# feather-load-tester-relabeled.net
KiCad netlist of a schematic drawn in EAGLE
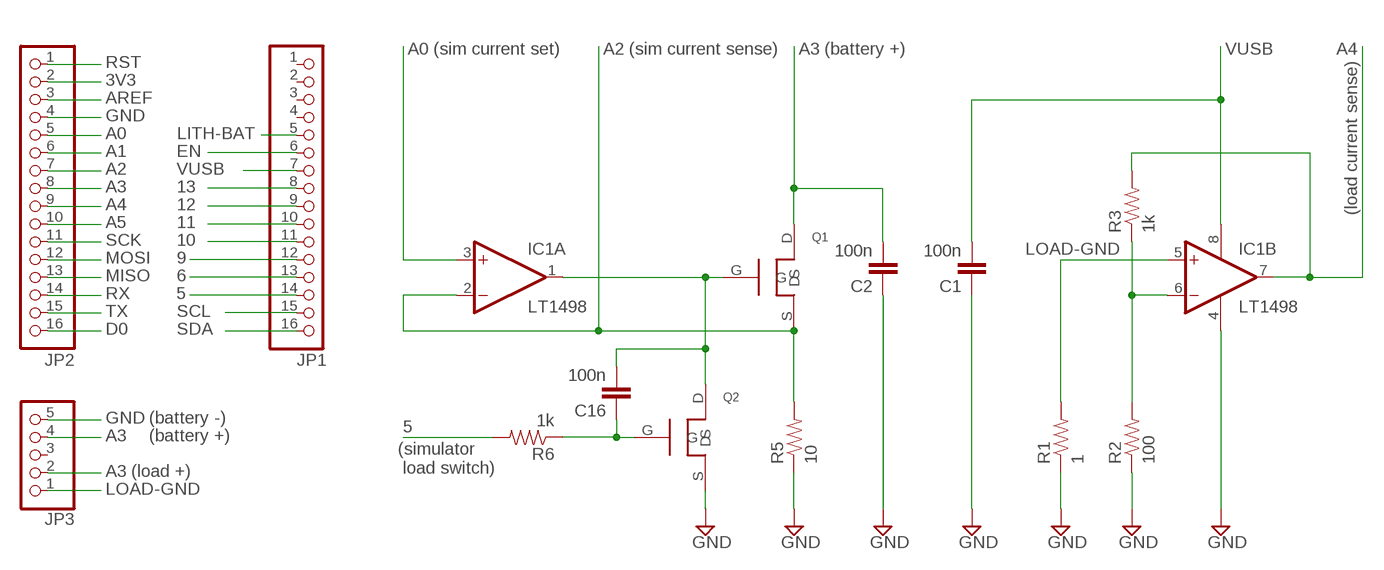
[diagram p0: schematic, sheet 1]

(export (version "E")
  (design (tool "Eeschema 10.0.6"))
  (components
    (comp (ref "C1")
      (value "100n")
      (footprint "eagle-import:0805-CAP")
      (libsource (lib "eagle-import") (part "0.33UF-50V-10%(0805)"))
    )
    (comp (ref "C2")
      (value "100n")
      (footprint "eagle-import:0805-CAP")
      (libsource (lib "eagle-import") (part "0.33UF-50V-10%(0805)"))
    )
    (comp (ref "C16")
      (value "100n")
      (footprint "eagle-import:0805-CAP")
      (libsource (lib "eagle-import") (part "0.33UF-50V-10%(0805)"))
    )
    (comp (ref "IC1")
      (value "LT1498")
      (footprint "eagle-import:SO08")
      (libsource (lib "eagle-import") (part "2AMP_P8+4D"))
    )
    (comp (ref "JP1")
      (value "PINHD-1X16")
      (footprint "eagle-import:1X16")
      (libsource (lib "eagle-import") (part "PINHD-1X16"))
    )
    (comp (ref "JP2")
      (value "PINHD-1X16")
      (footprint "eagle-import:1X16")
      (libsource (lib "eagle-import") (part "PINHD-1X16"))
    )
    (comp (ref "JP3")
      (value "PINHD-1X5")
      (footprint "eagle-import:1X05")
      (libsource (lib "eagle-import") (part "PINHD-1X5"))
    )
    (comp (ref "Q1")
      (value "NMOSFET_SC59")
      (footprint "eagle-import:SC59")
      (fields (field (name "MANUFACTURER") "Diodes Inc.") (field (name "MPN") "DMN1019UFDE-7"))
      (libsource (lib "eagle-import") (part "NMOSFET_SC59"))
    )
    (comp (ref "Q2")
      (value "NMOSFET_SC59")
      (footprint "eagle-import:SC59")
      (fields (field (name "MANUFACTURER") "Diodes Inc.") (field (name "MPN") "DMN1019UFDE-7"))
      (libsource (lib "eagle-import") (part "NMOSFET_SC59"))
    )
    (comp (ref "R1")
      (value "1")
      (footprint "eagle-import:0805")
      (libsource (lib "eagle-import") (part "0.22OHM-1/4W-1%(0805)"))
    )
    (comp (ref "R2")
      (value "100")
      (footprint "eagle-import:0805")
      (libsource (lib "eagle-import") (part "0.22OHM-1/4W-1%(0805)"))
    )
    (comp (ref "R3")
      (value "1k")
      (footprint "eagle-import:0805")
      (libsource (lib "eagle-import") (part "0.22OHM-1/4W-1%(0805)"))
    )
    (comp (ref "R5")
      (value "10")
      (footprint "eagle-import:0805")
      (libsource (lib "eagle-import") (part "0.22OHM-1/4W-1%(0805)"))
    )
    (comp (ref "R6")
      (value "1k")
      (footprint "eagle-import:0805")
      (libsource (lib "eagle-import") (part "0.22OHM-1/4W-1%(0805)"))
    )
  )
  (nets
    (net (code "1") (name "/3V3") (class "Default")
      (node (ref "JP2") (pin "2") (pinfunction "2_2") (pintype "passive"))
    )
    (net (code "2") (name "/5") (class "Default")
      (node (ref "JP1") (pin "14") (pinfunction "14_14") (pintype "passive"))
      (node (ref "R6") (pin "2") (pinfunction "2_2") (pintype "passive"))
    )
    (net (code "3") (name "/6") (class "Default")
      (node (ref "JP1") (pin "13") (pinfunction "13_13") (pintype "passive"))
    )
    (net (code "4") (name "/9") (class "Default")
      (node (ref "JP1") (pin "12") (pinfunction "12_12") (pintype "passive"))
    )
    (net (code "5") (name "/10") (class "Default")
      (node (ref "JP1") (pin "11") (pinfunction "11_11") (pintype "passive"))
    )
    (net (code "6") (name "/11") (class "Default")
      (node (ref "JP1") (pin "10") (pinfunction "10_10") (pintype "passive"))
    )
    (net (code "7") (name "/12") (class "Default")
      (node (ref "JP1") (pin "9") (pinfunction "9_9") (pintype "passive"))
    )
    (net (code "8") (name "/13") (class "Default")
      (node (ref "JP1") (pin "8") (pinfunction "8_8") (pintype "passive"))
    )
    (net (code "9") (name "/A0") (class "Default")
      (node (ref "IC1") (pin "3") (pinfunction "+IN_3") (pintype "input"))
      (node (ref "JP2") (pin "5") (pinfunction "5_5") (pintype "passive"))
    )
    (net (code "10") (name "/A1") (class "Default")
      (node (ref "JP2") (pin "6") (pinfunction "6_6") (pintype "passive"))
    )
    (net (code "11") (name "/A2") (class "Default")
      (node (ref "IC1") (pin "2") (pinfunction "-IN_2") (pintype "input"))
      (node (ref "JP2") (pin "7") (pinfunction "7_7") (pintype "passive"))
      (node (ref "Q1") (pin "S") (pinfunction "S_S") (pintype "bidirectional"))
      (node (ref "R5") (pin "2") (pinfunction "2_2") (pintype "passive"))
    )
    (net (code "12") (name "/A3") (class "Default")
      (node (ref "C2") (pin "2") (pinfunction "2_2") (pintype "passive"))
      (node (ref "JP2") (pin "8") (pinfunction "8_8") (pintype "passive"))
      (node (ref "JP3") (pin "2") (pinfunction "2_2") (pintype "passive"))
      (node (ref "JP3") (pin "4") (pinfunction "4_4") (pintype "passive"))
      (node (ref "Q1") (pin "D") (pinfunction "D_D") (pintype "bidirectional"))
    )
    (net (code "13") (name "/A4") (class "Default")
      (node (ref "IC1") (pin "7") (pinfunction "OUT_7") (pintype "output"))
      (node (ref "JP2") (pin "9") (pinfunction "9_9") (pintype "passive"))
      (node (ref "R3") (pin "2") (pinfunction "2_2") (pintype "passive"))
    )
    (net (code "14") (name "/A5") (class "Default")
      (node (ref "JP2") (pin "10") (pinfunction "10_10") (pintype "passive"))
    )
    (net (code "15") (name "/AREF") (class "Default")
      (node (ref "JP2") (pin "3") (pinfunction "3_3") (pintype "passive"))
    )
    (net (code "16") (name "/D0") (class "Default")
      (node (ref "JP2") (pin "16") (pinfunction "16_16") (pintype "passive"))
    )
    (net (code "17") (name "/EN") (class "Default")
      (node (ref "JP1") (pin "6") (pinfunction "6_6") (pintype "passive"))
    )
    (net (code "18") (name "/LITH-BAT") (class "Default")
      (node (ref "JP1") (pin "5") (pinfunction "5_5") (pintype "passive"))
    )
    (net (code "19") (name "/LOAD-GND") (class "Default")
      (node (ref "IC1") (pin "5") (pinfunction "+IN_5") (pintype "input"))
      (node (ref "JP3") (pin "1") (pinfunction "1_1") (pintype "passive"))
      (node (ref "R1") (pin "2") (pinfunction "2_2") (pintype "passive"))
    )
    (net (code "20") (name "/MISO") (class "Default")
      (node (ref "JP2") (pin "13") (pinfunction "13_13") (pintype "passive"))
    )
    (net (code "21") (name "/MOSI") (class "Default")
      (node (ref "JP2") (pin "12") (pinfunction "12_12") (pintype "passive"))
    )
    (net (code "22") (name "/RST") (class "Default")
      (node (ref "JP2") (pin "1") (pinfunction "1_1") (pintype "passive"))
    )
    (net (code "23") (name "/RX") (class "Default")
      (node (ref "JP2") (pin "14") (pinfunction "14_14") (pintype "passive"))
    )
    (net (code "24") (name "/SCK") (class "Default")
      (node (ref "JP2") (pin "11") (pinfunction "11_11") (pintype "passive"))
    )
    (net (code "25") (name "/SCL") (class "Default")
      (node (ref "JP1") (pin "15") (pinfunction "15_15") (pintype "passive"))
    )
    (net (code "26") (name "/SDA") (class "Default")
      (node (ref "JP1") (pin "16") (pinfunction "16_16") (pintype "passive"))
    )
    (net (code "27") (name "/TX") (class "Default")
      (node (ref "JP2") (pin "15") (pinfunction "15_15") (pintype "passive"))
    )
    (net (code "28") (name "/VUSB") (class "Default")
      (node (ref "C1") (pin "2") (pinfunction "2_2") (pintype "passive"))
      (node (ref "IC1") (pin "8") (pinfunction "V+_8") (pintype "power_in"))
      (node (ref "JP1") (pin "7") (pinfunction "7_7") (pintype "passive"))
    )
    (net (code "29") (name "GND") (class "Default")
      (node (ref "C1") (pin "1") (pinfunction "1_1") (pintype "passive"))
      (node (ref "C2") (pin "1") (pinfunction "1_1") (pintype "passive"))
      (node (ref "IC1") (pin "4") (pinfunction "V-_4") (pintype "power_in"))
      (node (ref "JP2") (pin "4") (pinfunction "4_4") (pintype "passive"))
      (node (ref "JP3") (pin "5") (pinfunction "5_5") (pintype "passive"))
      (node (ref "Q2") (pin "S") (pinfunction "S_S") (pintype "bidirectional"))
      (node (ref "R1") (pin "1") (pinfunction "1_1") (pintype "passive"))
      (node (ref "R2") (pin "1") (pinfunction "1_1") (pintype "passive"))
      (node (ref "R5") (pin "1") (pinfunction "1_1") (pintype "passive"))
    )
    (net (code "30") (name "Net-(C16-Pad1)") (class "Default")
      (node (ref "C16") (pin "1") (pinfunction "1_1") (pintype "passive"))
      (node (ref "Q2") (pin "G") (pinfunction "G_G") (pintype "bidirectional"))
      (node (ref "R6") (pin "1") (pinfunction "1_1") (pintype "passive"))
    )
    (net (code "31") (name "Net-(IC1A-OUT)") (class "Default")
      (node (ref "C16") (pin "2") (pinfunction "2_2") (pintype "passive"))
      (node (ref "IC1") (pin "1") (pinfunction "OUT_1") (pintype "output"))
      (node (ref "Q1") (pin "G") (pinfunction "G_G") (pintype "bidirectional"))
      (node (ref "Q2") (pin "D") (pinfunction "D_D") (pintype "bidirectional"))
    )
    (net (code "32") (name "Net-(IC1B--IN)") (class "Default")
      (node (ref "IC1") (pin "6") (pinfunction "-IN_6") (pintype "input"))
      (node (ref "R2") (pin "2") (pinfunction "2_2") (pintype "passive"))
      (node (ref "R3") (pin "1") (pinfunction "1_1") (pintype "passive"))
    )
    (net (code "33") (name "unconnected-(JP1-Pad1)") (class "Default")
      (node (ref "JP1") (pin "1") (pinfunction "1_1") (pintype "passive"))
    )
    (net (code "34") (name "unconnected-(JP1-Pad2)") (class "Default")
      (node (ref "JP1") (pin "2") (pinfunction "2_2") (pintype "passive"))
    )
    (net (code "35") (name "unconnected-(JP1-Pad3)") (class "Default")
      (node (ref "JP1") (pin "3") (pinfunction "3_3") (pintype "passive"))
    )
    (net (code "36") (name "unconnected-(JP1-Pad4)") (class "Default")
      (node (ref "JP1") (pin "4") (pinfunction "4_4") (pintype "passive"))
    )
    (net (code "37") (name "unconnected-(JP3-Pad3)") (class "Default")
      (node (ref "JP3") (pin "3") (pinfunction "3_3") (pintype "passive"))
    )
  )
)
